# SHDN-S09-V00-Buzzer.net
KiCad netlist of a schematic drawn in Altium Designer
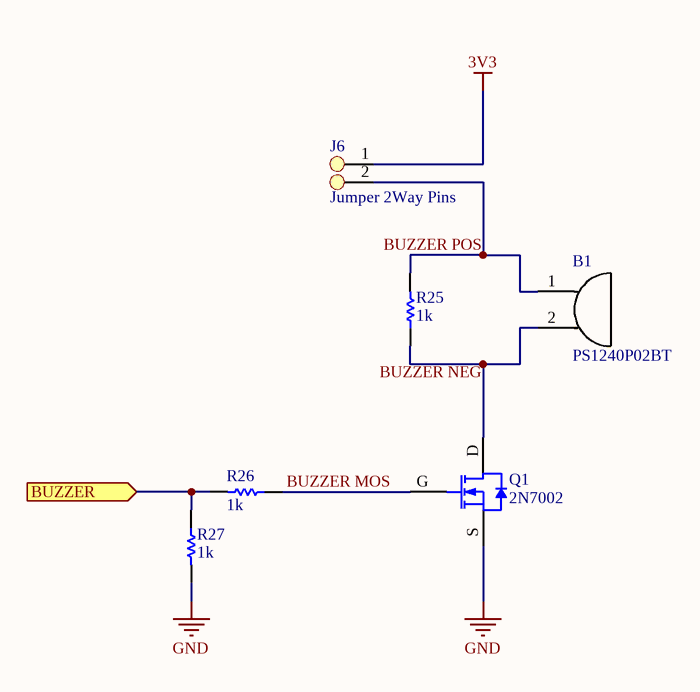
[diagram p0: SHDN-S09-V00-Buzzer.SchDoc]

(export (version "E")
  (design (tool "Eeschema 10.0.6"))
  (components
    (comp (ref "B1")
      (value "PS1240P02BT")
      (footprint "PS1240P02BT")
      (description "Buzzers Transducer, Externally Driven Piezo 3V 4kHz 60dB @ 3V, 10cm Through Hole PC Pins")
      (libsource (lib "QUTMS_BuzzerLibrary") (part "PS1240P02BT"))
    )
    (comp (ref "J6")
      (value "Jumper 2Way Pins")
      (footprint "Jumper_2Way_Pin")
      (description "Jumper 2Way Side Pins")
      (libsource (lib "QUTMS_JumperLibrary") (part "Jumper 2Way Side Pins"))
    )
    (comp (ref "Q1")
      (value "2N7002")
      (footprint "SOT23-3")
      (libsource (lib "QUTMS_MOSFETLibrary") (part "2N7002"))
    )
    (comp (ref "R25")
      (value "1k")
      (footprint "Res_ThinFilm_0603")
      (description "Resistor, SMD, 1k, 0.1W, 5%, 0603")
      (libsource (lib "StandardResistors") (part "1k 5% 0603"))
    )
    (comp (ref "R26")
      (value "1k")
      (footprint "Res_ThinFilm_0603")
      (description "Resistor, SMD, 1k, 0.1W, 5%, 0603")
      (libsource (lib "StandardResistors") (part "1k 5% 0603"))
    )
    (comp (ref "R27")
      (value "1k")
      (footprint "Res_ThinFilm_0603")
      (description "Resistor, SMD, 1k, 0.1W, 5%, 0603")
      (libsource (lib "StandardResistors") (part "1k 5% 0603"))
    )
  )
  (nets
    (net (code "1") (name "/BUZZER") (class "Default")
      (node (ref "R26") (pin "2") (pinfunction "2_2") (pintype "passive"))
      (node (ref "R27") (pin "1") (pinfunction "1_1") (pintype "passive"))
    )
    (net (code "2") (name "/BUZZER MOS") (class "Default")
      (node (ref "Q1") (pin "G") (pinfunction "G_G") (pintype "passive"))
      (node (ref "R26") (pin "1") (pinfunction "1_1") (pintype "passive"))
    )
    (net (code "3") (name "/BUZZER NEG") (class "Default")
      (node (ref "B1") (pin "2") (pinfunction "2_2") (pintype "passive"))
      (node (ref "Q1") (pin "D") (pinfunction "D_D") (pintype "passive"))
      (node (ref "R25") (pin "1") (pinfunction "1_1") (pintype "passive"))
    )
    (net (code "4") (name "/BUZZER POS") (class "Default")
      (node (ref "B1") (pin "1") (pinfunction "1_1") (pintype "passive"))
      (node (ref "J6") (pin "2") (pinfunction "2_2") (pintype "passive"))
      (node (ref "R25") (pin "2") (pinfunction "2_2") (pintype "passive"))
    )
    (net (code "5") (name "3V3") (class "Default")
      (node (ref "J6") (pin "1") (pinfunction "1_1") (pintype "passive"))
    )
    (net (code "6") (name "GND") (class "Default")
      (node (ref "Q1") (pin "S") (pinfunction "S_S") (pintype "passive"))
      (node (ref "R27") (pin "2") (pinfunction "2_2") (pintype "passive"))
    )
  )
)
